# H0FR6.net
KiCad netlist of a schematic drawn in EAGLE
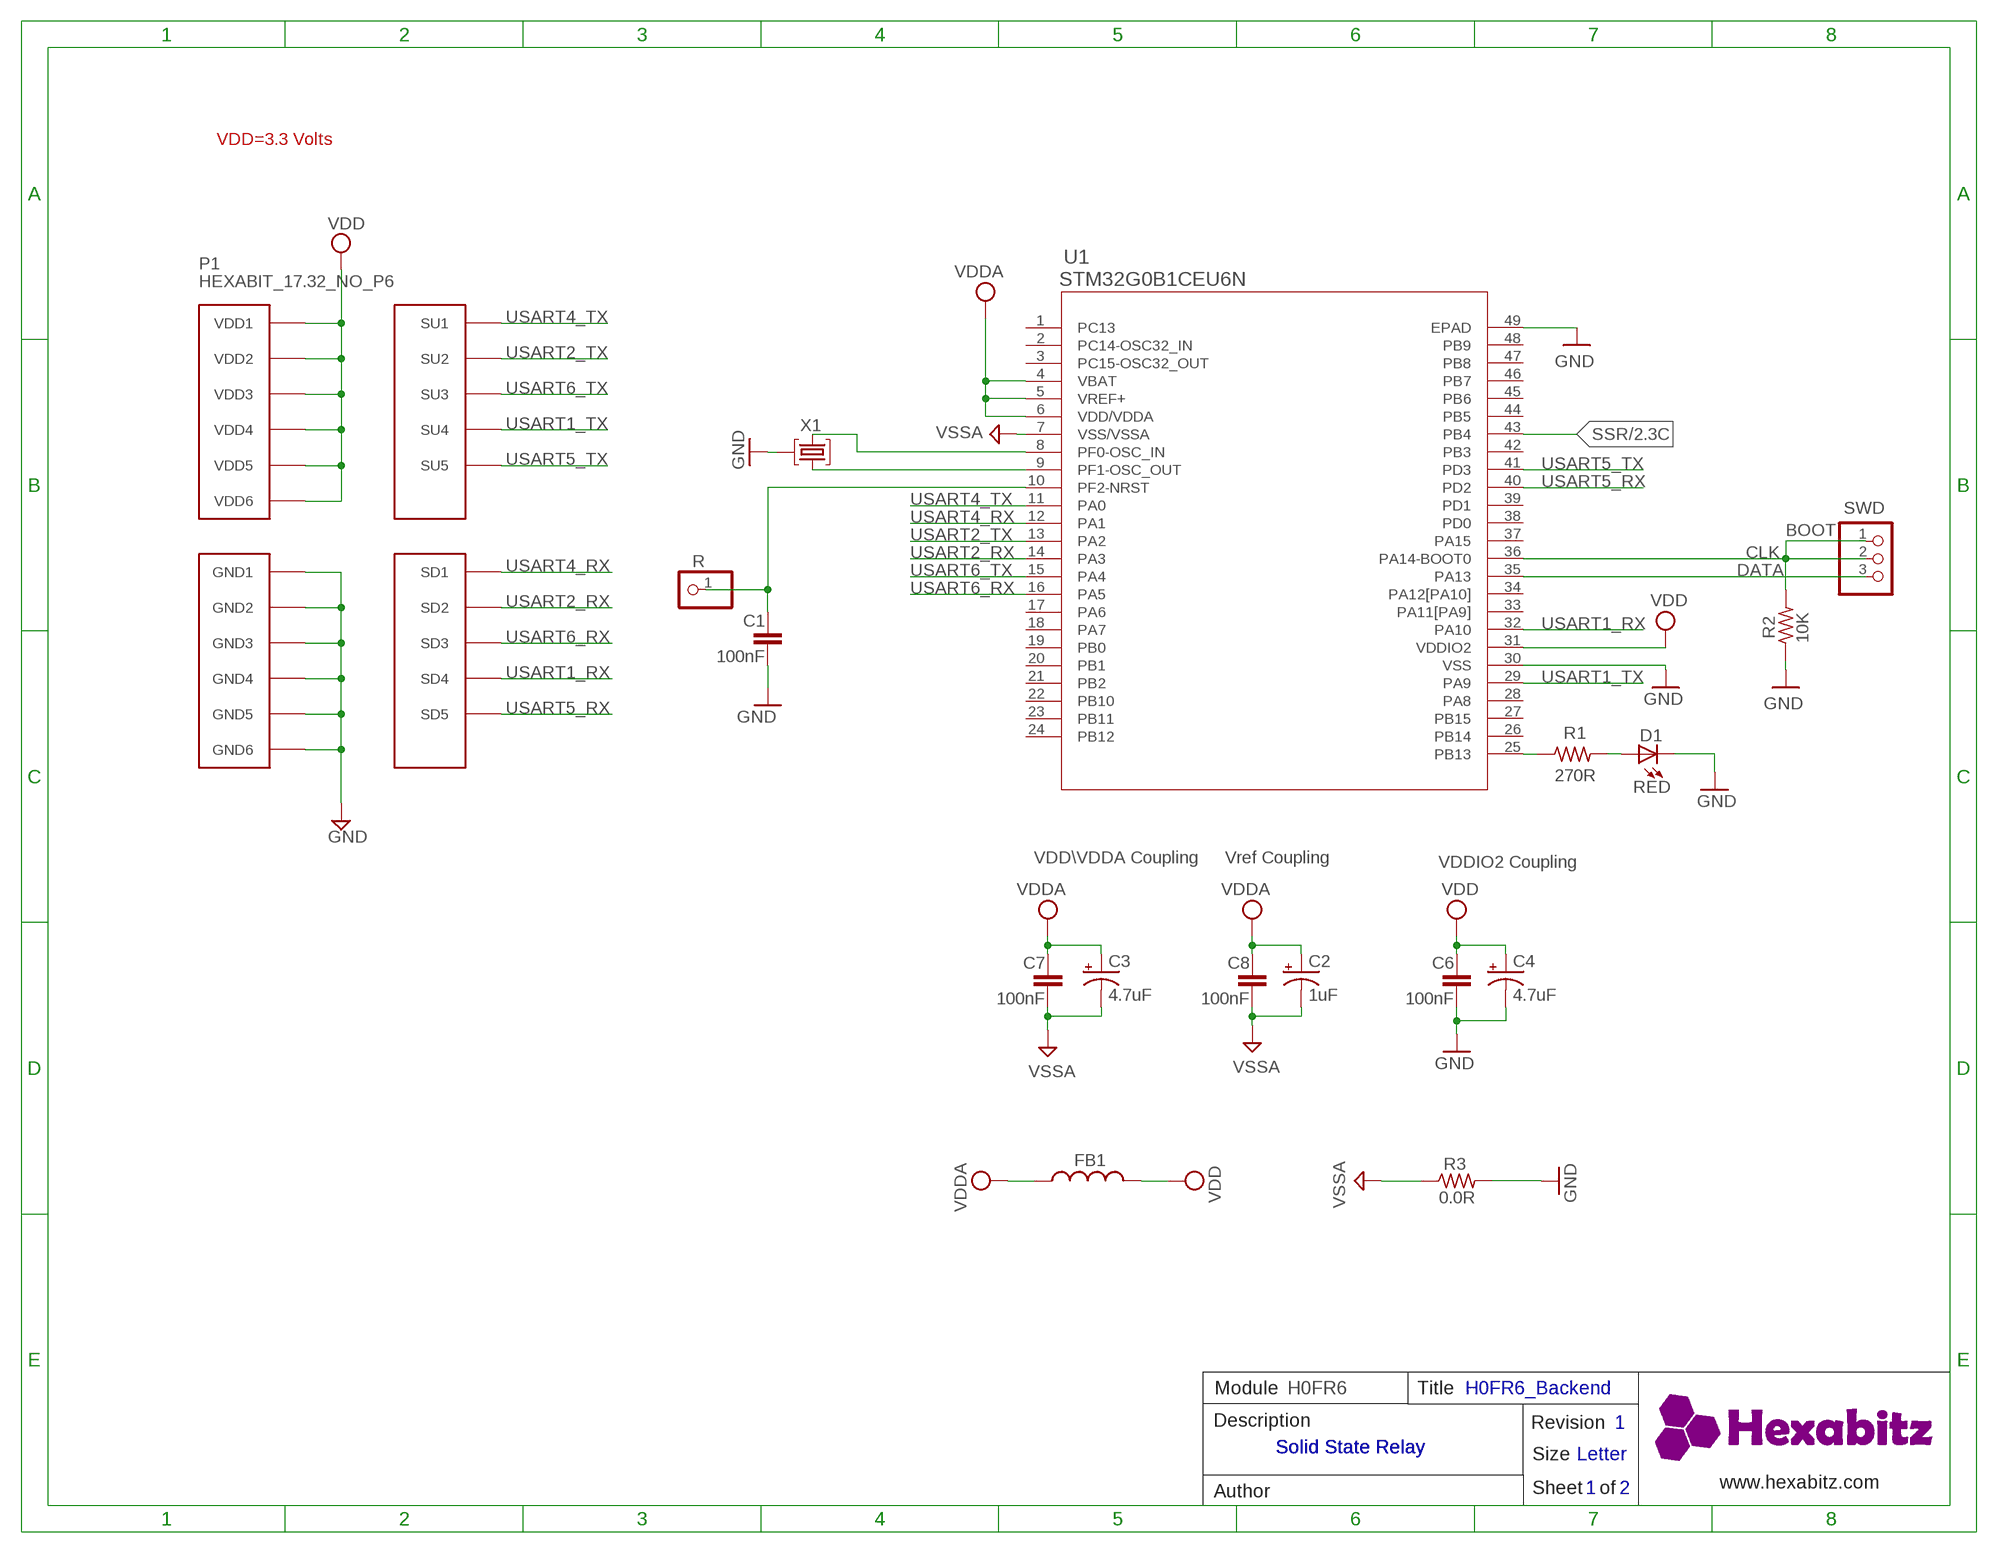
[diagram p0: schematic, sheet 1]
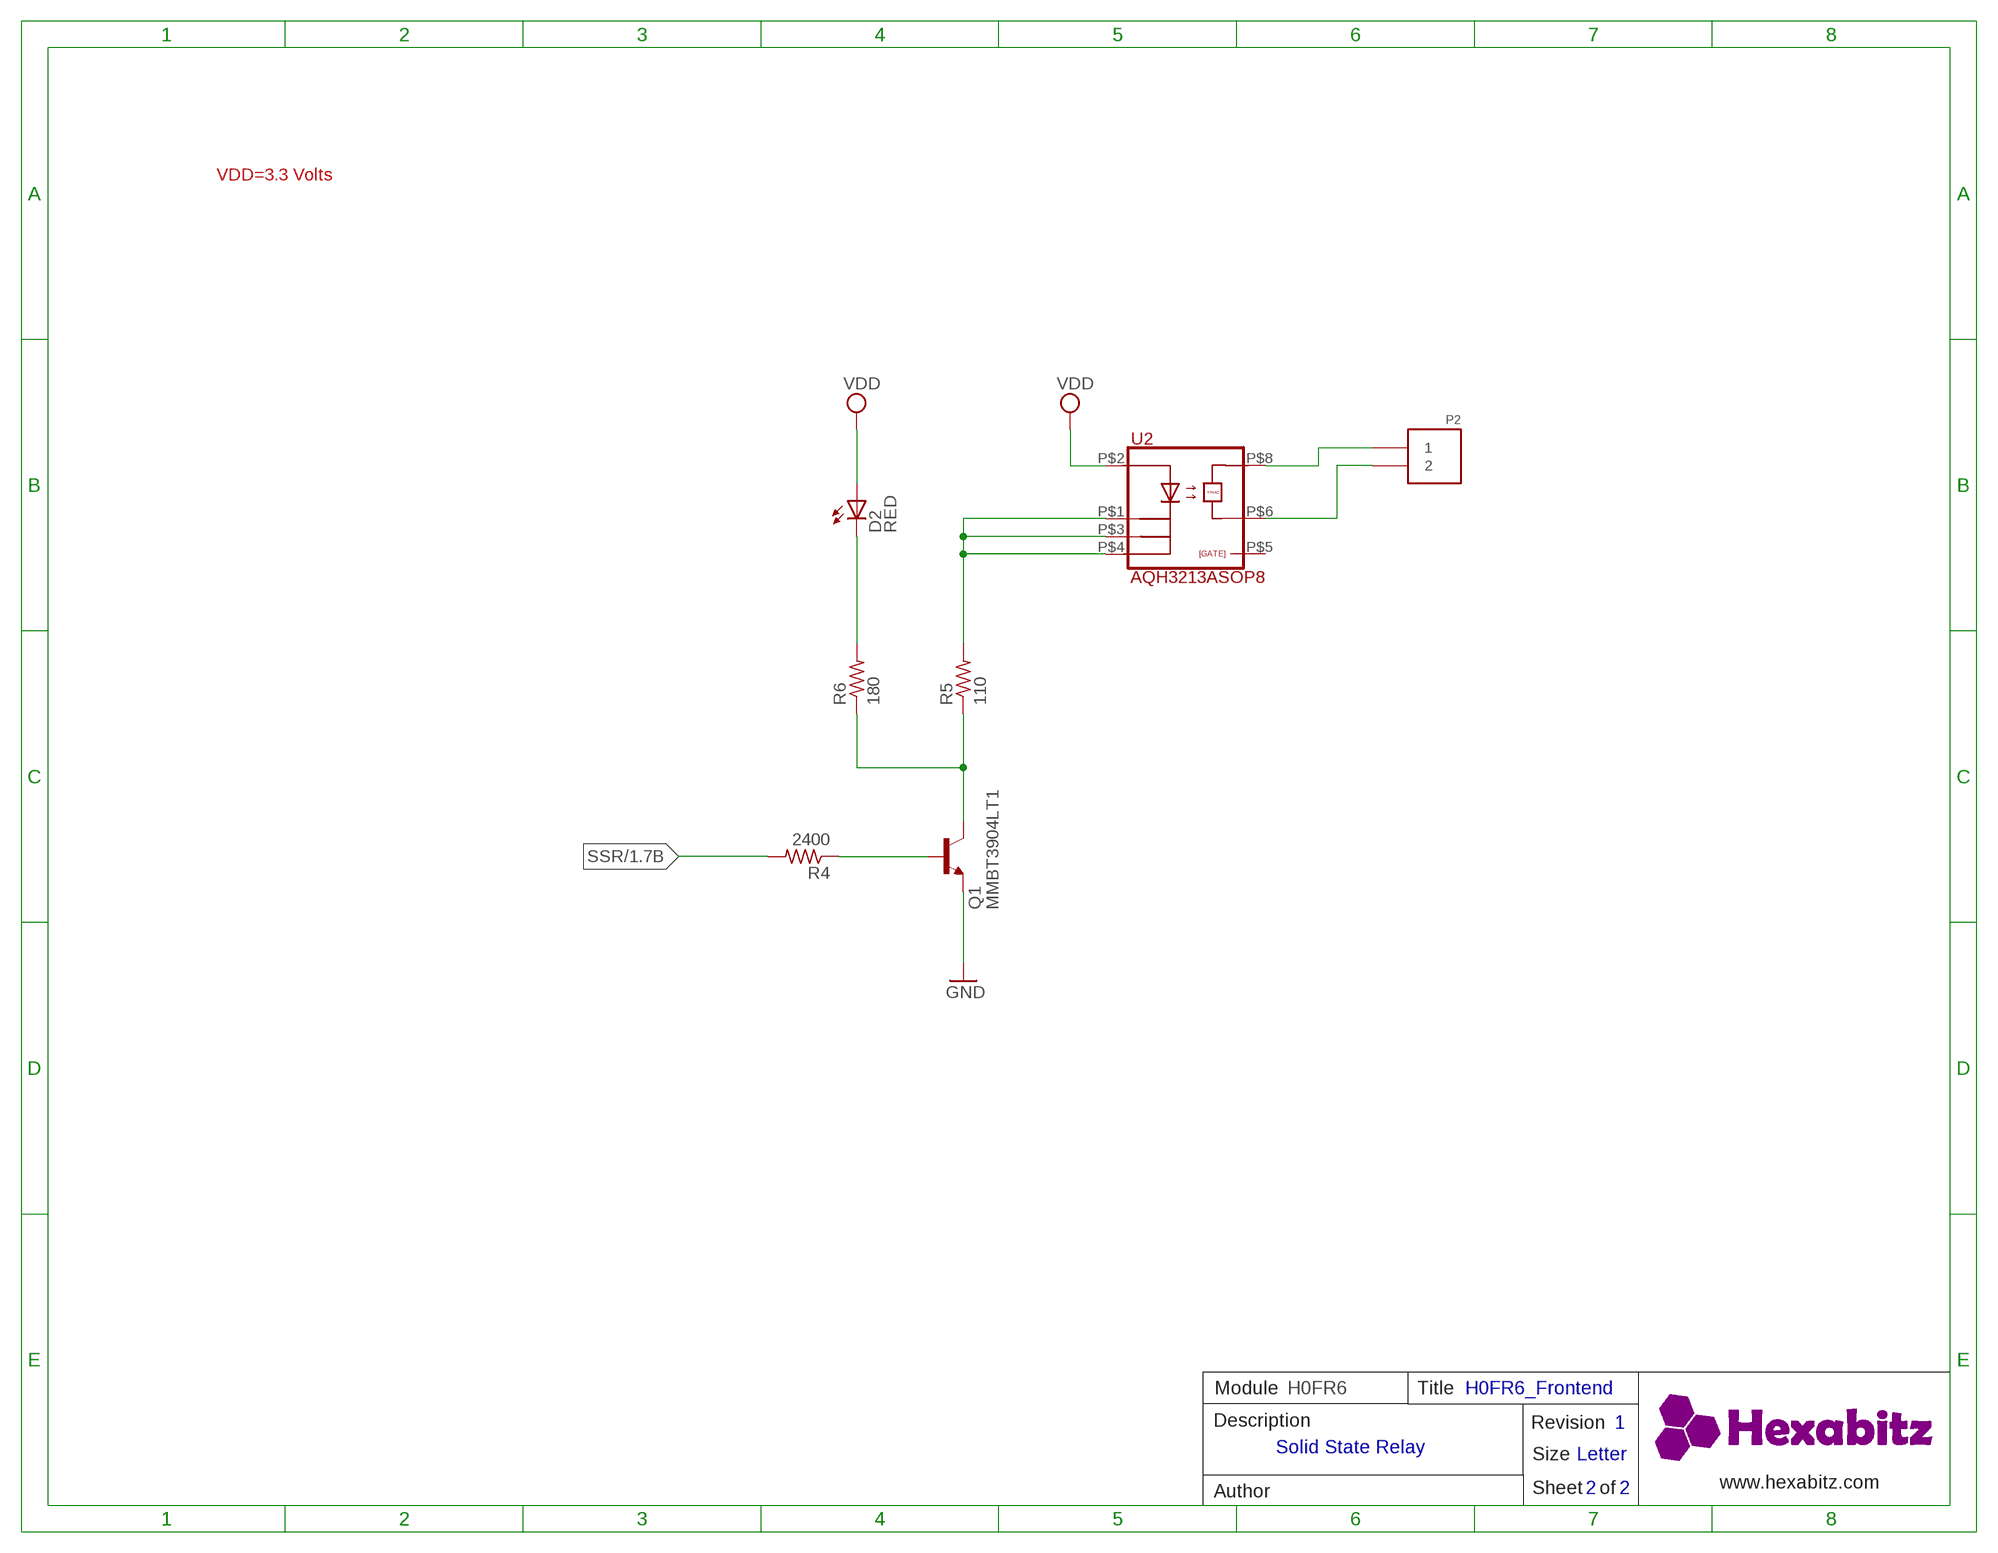
[diagram p1: schematic, sheet 2]

(export (version "E")
  (design (tool "Eeschema 10.0.6"))
  (components
    (comp (ref "D2")
      (value "RED")
      (footprint "eagle-import:VLMS1300-GS08")
      (fields
        (field (name "MPN") "VLMS1300-GS08")
        (field (name "MFN") "Vishay ")
        (field (name "MPN_1") "VLMY1300-GS08")
        (field (name "OCTOPART_URL") "https://octopart.com/vlmy1300-gs08-vishay-21709204")
      )
      (libsource (lib "eagle-import") (part "VLMS1300-GS08"))
    )
    (comp (ref "P2")
      (value "1546111-2")
      (footprint "eagle-import:1546111-2")
      (libsource (lib "eagle-import") (part "1546111-2"))
    )
    (comp (ref "Q1")
      (value "MMBT3904LT1")
      (footprint "eagle-import:MMBT3904LT1")
      (fields
        (field (name "MFN") "ON Semiconductor")
        (field (name "MPN") "MMBT3904LT1G")
        (field (name "OCTOPART_ID") "0bb6c2bc2200d471")
        (field (name "OCTOPART_URL") "http://octopart.com/mmbt3904lt1g-on+semiconductor-3280")
        (field (name "POLARITY") "NPN")
        (field (name "POWER_DISSIPATION") "0.225 W")
        (field (name "VOLTAGE_RATING_DC") "40.0 V")
      )
      (libsource (lib "eagle-import") (part "MMBT3904LT1"))
    )
    (comp (ref "R4")
      (value "2400")
      (footprint "eagle-import:R-0603")
      (fields
        (field (name "MFN") "Yageo")
        (field (name "MPN") "RC0603JR-070RL")
        (field (name "OCTOPART_URL") "https://octopart.com/crcw06032k40jnea-vishay-40298967")
        (field (name "RESISTANCE") "2400.0 Ω")
        (field (name "TOLERANCE") "±5%")
      )
      (libsource (lib "eagle-import") (part "R-0603"))
    )
    (comp (ref "R5")
      (value "110")
      (footprint "eagle-import:R-0603")
      (fields
        (field (name "MFN") "Yageo")
        (field (name "MPN") "RC0402FR-07100RL")
        (field (name "OCTOPART_URL") "https://octopart.com/crcw0603110rfkea-vishay-39455532")
        (field (name "RESISTANCE") "110.0 Ω")
        (field (name "TOLERANCE") "±1%")
      )
      (libsource (lib "eagle-import") (part "R-0603"))
    )
    (comp (ref "R6")
      (value "180")
      (footprint "eagle-import:R-0603")
      (fields
        (field (name "MFN") "Yageo")
        (field (name "MPN") "RC0402FR-07100RL")
        (field (name "OCTOPART_URL") "https://octopart.com/erj-3geyj181v-panasonic-55403673")
        (field (name "RESISTANCE") "180.0 Ω")
        (field (name "TOLERANCE") "±5%")
      )
      (libsource (lib "eagle-import") (part "R-0603"))
    )
    (comp (ref "U2")
      (value "AQH3213ASOP8")
      (footprint "eagle-import:AQH3213A")
      (libsource (lib "eagle-import") (part "AQH3213ASOP8"))
    )
    (comp (ref "C1")
      (value "100nF")
      (footprint "eagle-import:C-0603")
      (libsource (lib "eagle-import") (part "C-0603"))
    )
    (comp (ref "C2")
      (value "1uF")
      (footprint "eagle-import:C-0805-POL")
      (libsource (lib "eagle-import") (part "C-0805-POL"))
    )
    (comp (ref "C3")
      (value "4.7uF")
      (footprint "eagle-import:C-0805-POL")
      (libsource (lib "eagle-import") (part "C-0805-POL"))
    )
    (comp (ref "C4")
      (value "4.7uF")
      (footprint "eagle-import:C-0805-POL")
      (libsource (lib "eagle-import") (part "C-0805-POL"))
    )
    (comp (ref "C6")
      (value "100nF")
      (footprint "eagle-import:C-0603")
      (libsource (lib "eagle-import") (part "C-0603"))
    )
    (comp (ref "C7")
      (value "100nF")
      (footprint "eagle-import:C-0603")
      (libsource (lib "eagle-import") (part "C-0603"))
    )
    (comp (ref "C8")
      (value "100nF")
      (footprint "eagle-import:C-0603")
      (libsource (lib "eagle-import") (part "C-0603"))
    )
    (comp (ref "D1")
      (value "RED")
      (footprint "eagle-import:VLMS1300-GS08")
      (fields
        (field (name "MPN") "VLMS1300-GS08")
        (field (name "MFN") "Vishay")
        (field (name "MPN_1") "VLMS1300-GS08")
        (field (name "OCTOPART_URL") "https://octopart.com/vlms1300-gs08-vishay-21709201?r=sp&s=_gcP4_q8T1SC6PJQPTQ9yA")
      )
      (libsource (lib "eagle-import") (part "VLMS1300-GS08"))
    )
    (comp (ref "FB1")
      (value "FB-0603")
      (footprint "eagle-import:FB-0603")
      (libsource (lib "eagle-import") (part "FB-0603"))
    )
    (comp (ref "P1")
      (value "HEXABIT_17.32_NO_P6")
      (footprint "eagle-import:HEXABIT_17.32_NO_P6")
      (libsource (lib "eagle-import") (part "HEXABIT_?_NO_P617.32"))
    )
    (comp (ref "R")
      (value "R")
      (footprint "eagle-import:1X01")
      (fields (field (name "MPN") "87227-1"))
      (libsource (lib "eagle-import") (part "PINHD-1X1"))
    )
    (comp (ref "R1")
      (value "270R")
      (footprint "eagle-import:R-0603")
      (libsource (lib "eagle-import") (part "R-0603"))
    )
    (comp (ref "R2")
      (value "10K")
      (footprint "eagle-import:R-0603")
      (libsource (lib "eagle-import") (part "R-0603"))
    )
    (comp (ref "R3")
      (value "0.0R")
      (footprint "eagle-import:R-0603")
      (libsource (lib "eagle-import") (part "R-0603"))
    )
    (comp (ref "SWD")
      (value "PINHD-1X3")
      (footprint "eagle-import:1X03")
      (libsource (lib "eagle-import") (part "PINHD-1X3"))
    )
    (comp (ref "U1")
      (value "STM32G0B1CEU6N")
      (footprint "eagle-import:HEXABITZ_ICS_QFN_B1CEU6_STM-L")
      (libsource (lib "eagle-import") (part "STM32G0B1CEU6N"))
    )
    (comp (ref "X1")
      (value "XTALL_CSTCE8M00G52")
      (footprint "eagle-import:XTALL_CSTCE8M00G52")
      (fields (field (name "MPN") "CSTCE8M00G52Z-R0"))
      (libsource (lib "eagle-import") (part "XTALL_CSTCE8M00G52"))
    )
  )
  (nets
    (net (code "1") (name "CLK") (class "Default")
      (node (ref "R2") (pin "2") (pinfunction "2_2") (pintype "passive"))
      (node (ref "SWD") (pin "1") (pinfunction "1_1") (pintype "passive"))
      (node (ref "SWD") (pin "2") (pinfunction "2_2") (pintype "passive"))
      (node (ref "U1") (pin "36") (pinfunction "PA14-BOOT0_36") (pintype "bidirectional"))
    )
    (net (code "2") (name "DATA") (class "Default")
      (node (ref "SWD") (pin "3") (pinfunction "3_3") (pintype "passive"))
      (node (ref "U1") (pin "35") (pinfunction "PA13_35") (pintype "bidirectional"))
    )
    (net (code "3") (name "GND") (class "Default")
      (node (ref "C1") (pin "2") (pinfunction "2_2") (pintype "passive"))
      (node (ref "C4") (pin "2") (pinfunction "-_2") (pintype "passive"))
      (node (ref "C6") (pin "2") (pinfunction "2_2") (pintype "passive"))
      (node (ref "D1") (pin "C") (pinfunction "C_C") (pintype "passive"))
      (node (ref "P1") (pin "PAD_PD10") (pinfunction "GND4_PAD_PD10") (pintype "power_in"))
      (node (ref "P1") (pin "PAD_PD11") (pinfunction "GND5_PAD_PD11") (pintype "power_in"))
      (node (ref "P1") (pin "PAD_PD12") (pinfunction "GND6_PAD_PD12") (pintype "power_in"))
      (node (ref "P1") (pin "PAD_PD7") (pinfunction "GND1_PAD_PD7") (pintype "power_in"))
      (node (ref "P1") (pin "PAD_PD8") (pinfunction "GND2_PAD_PD8") (pintype "power_in"))
      (node (ref "P1") (pin "PAD_PD9") (pinfunction "GND3_PAD_PD9") (pintype "power_in"))
      (node (ref "Q1") (pin "2") (pinfunction "E_2") (pintype "passive"))
      (node (ref "R2") (pin "1") (pinfunction "1_1") (pintype "passive"))
      (node (ref "R3") (pin "2") (pinfunction "2_2") (pintype "passive"))
      (node (ref "U1") (pin "30") (pinfunction "VSS_30") (pintype "passive"))
      (node (ref "U1") (pin "49") (pinfunction "EPAD_49") (pintype "passive"))
      (node (ref "X1") (pin "P$2") (pinfunction "2_P$2") (pintype "passive"))
    )
    (net (code "4") (name "Net-(D1-PadA)") (class "Default")
      (node (ref "D1") (pin "A") (pinfunction "A_A") (pintype "passive"))
      (node (ref "R1") (pin "2") (pinfunction "2_2") (pintype "passive"))
    )
    (net (code "5") (name "Net-(D2-PadC)") (class "Default")
      (node (ref "D2") (pin "C") (pinfunction "C_C") (pintype "passive"))
      (node (ref "R6") (pin "2") (pinfunction "2_2") (pintype "passive"))
    )
    (net (code "6") (name "Net-(P2-Pad2)") (class "Default")
      (node (ref "P2") (pin "2") (pinfunction "2_2") (pintype "power_in"))
      (node (ref "U2") (pin "P$6") (pinfunction "P$6_P$6") (pintype "bidirectional"))
    )
    (net (code "7") (name "Net-(Q1-B)") (class "Default")
      (node (ref "Q1") (pin "1") (pinfunction "B_1") (pintype "passive"))
      (node (ref "R4") (pin "1") (pinfunction "1_1") (pintype "passive"))
    )
    (net (code "8") (name "Net-(Q1-C)") (class "Default")
      (node (ref "Q1") (pin "3") (pinfunction "C_3") (pintype "passive"))
      (node (ref "R5") (pin "1") (pinfunction "1_1") (pintype "passive"))
      (node (ref "R6") (pin "1") (pinfunction "1_1") (pintype "passive"))
    )
    (net (code "9") (name "Net-(R5-Pad2)") (class "Default")
      (node (ref "R5") (pin "2") (pinfunction "2_2") (pintype "passive"))
      (node (ref "U2") (pin "P$1") (pinfunction "P$1_P$1") (pintype "bidirectional"))
      (node (ref "U2") (pin "P$3") (pinfunction "P$3_P$3") (pintype "bidirectional"))
      (node (ref "U2") (pin "P$4") (pinfunction "P$4_P$4") (pintype "bidirectional"))
    )
    (net (code "10") (name "Net-(U1-PB13)") (class "Default")
      (node (ref "R1") (pin "1") (pinfunction "1_1") (pintype "passive"))
      (node (ref "U1") (pin "25") (pinfunction "PB13_25") (pintype "bidirectional"))
    )
    (net (code "11") (name "Net-(U1-PF0-OSC_IN)") (class "Default")
      (node (ref "U1") (pin "8") (pinfunction "PF0-OSC_IN_8") (pintype "bidirectional"))
      (node (ref "X1") (pin "P$3") (pinfunction "3_P$3") (pintype "passive"))
    )
    (net (code "12") (name "Net-(U1-PF1-OSC_OUT)") (class "Default")
      (node (ref "U1") (pin "9") (pinfunction "PF1-OSC_OUT_9") (pintype "bidirectional"))
      (node (ref "X1") (pin "P$1") (pinfunction "1_P$1") (pintype "passive"))
    )
    (net (code "13") (name "Net-(U1-PF2-NRST)") (class "Default")
      (node (ref "C1") (pin "1") (pinfunction "1_1") (pintype "passive"))
      (node (ref "R") (pin "1") (pinfunction "1_1") (pintype "passive"))
      (node (ref "U1") (pin "10") (pinfunction "PF2-NRST_10") (pintype "bidirectional"))
    )
    (net (code "14") (name "Net-(U2-P$7)") (class "Default")
      (node (ref "P2") (pin "1") (pinfunction "1_1") (pintype "power_in"))
      (node (ref "U2") (pin "P$8") (pinfunction "P$7_P$8") (pintype "bidirectional"))
    )
    (net (code "15") (name "SSR") (class "Default")
      (node (ref "R4") (pin "2") (pinfunction "2_2") (pintype "passive"))
      (node (ref "U1") (pin "43") (pinfunction "PB4_43") (pintype "bidirectional"))
    )
    (net (code "16") (name "USART1_RX") (class "Default")
      (node (ref "P1") (pin "PAD_PD4") (pinfunction "SD4_PAD_PD4") (pintype "bidirectional"))
      (node (ref "U1") (pin "32") (pinfunction "PA10_32") (pintype "bidirectional"))
    )
    (net (code "17") (name "USART1_TX") (class "Default")
      (node (ref "P1") (pin "PAD_PU4") (pinfunction "SU4_PAD_PU4") (pintype "bidirectional"))
      (node (ref "U1") (pin "29") (pinfunction "PA9_29") (pintype "bidirectional"))
    )
    (net (code "18") (name "USART2_RX") (class "Default")
      (node (ref "P1") (pin "PAD_PD2") (pinfunction "SD2_PAD_PD2") (pintype "bidirectional"))
      (node (ref "U1") (pin "14") (pinfunction "PA3_14") (pintype "bidirectional"))
    )
    (net (code "19") (name "USART2_TX") (class "Default")
      (node (ref "P1") (pin "PAD_PU2") (pinfunction "SU2_PAD_PU2") (pintype "bidirectional"))
      (node (ref "U1") (pin "13") (pinfunction "PA2_13") (pintype "bidirectional"))
    )
    (net (code "20") (name "USART4_RX") (class "Default")
      (node (ref "P1") (pin "PAD_PD1") (pinfunction "SD1_PAD_PD1") (pintype "bidirectional"))
      (node (ref "U1") (pin "12") (pinfunction "PA1_12") (pintype "bidirectional"))
    )
    (net (code "21") (name "USART4_TX") (class "Default")
      (node (ref "P1") (pin "PAD_PU1") (pinfunction "SU1_PAD_PU1") (pintype "bidirectional"))
      (node (ref "U1") (pin "11") (pinfunction "PA0_11") (pintype "bidirectional"))
    )
    (net (code "22") (name "USART5_RX") (class "Default")
      (node (ref "P1") (pin "PAD_PD5") (pinfunction "SD5_PAD_PD5") (pintype "bidirectional"))
      (node (ref "U1") (pin "40") (pinfunction "PD2_40") (pintype "bidirectional"))
    )
    (net (code "23") (name "USART5_TX") (class "Default")
      (node (ref "P1") (pin "PAD_PU5") (pinfunction "SU5_PAD_PU5") (pintype "bidirectional"))
      (node (ref "U1") (pin "41") (pinfunction "PD3_41") (pintype "bidirectional"))
    )
    (net (code "24") (name "USART6_RX") (class "Default")
      (node (ref "P1") (pin "PAD_PD3") (pinfunction "SD3_PAD_PD3") (pintype "bidirectional"))
      (node (ref "U1") (pin "16") (pinfunction "PA5_16") (pintype "bidirectional"))
    )
    (net (code "25") (name "USART6_TX") (class "Default")
      (node (ref "P1") (pin "PAD_PU3") (pinfunction "SU3_PAD_PU3") (pintype "bidirectional"))
      (node (ref "U1") (pin "15") (pinfunction "PA4_15") (pintype "bidirectional"))
    )
    (net (code "26") (name "VDD") (class "Default")
      (node (ref "C4") (pin "1") (pinfunction "+_1") (pintype "passive"))
      (node (ref "C6") (pin "1") (pinfunction "1_1") (pintype "passive"))
      (node (ref "D2") (pin "A") (pinfunction "A_A") (pintype "passive"))
      (node (ref "FB1") (pin "2") (pinfunction "2_2") (pintype "passive"))
      (node (ref "P1") (pin "PAD_PU10") (pinfunction "VDD4_PAD_PU10") (pintype "power_in"))
      (node (ref "P1") (pin "PAD_PU11") (pinfunction "VDD5_PAD_PU11") (pintype "power_in"))
      (node (ref "P1") (pin "PAD_PU12") (pinfunction "VDD6_PAD_PU12") (pintype "power_in"))
      (node (ref "P1") (pin "PAD_PU7") (pinfunction "VDD1_PAD_PU7") (pintype "power_in"))
      (node (ref "P1") (pin "PAD_PU8") (pinfunction "VDD2_PAD_PU8") (pintype "power_in"))
      (node (ref "P1") (pin "PAD_PU9") (pinfunction "VDD3_PAD_PU9") (pintype "power_in"))
      (node (ref "U1") (pin "31") (pinfunction "VDDIO2_31") (pintype "power_in"))
      (node (ref "U2") (pin "P$2") (pinfunction "P$2_P$2") (pintype "bidirectional"))
    )
    (net (code "27") (name "VDDA") (class "Default")
      (node (ref "C2") (pin "1") (pinfunction "+_1") (pintype "passive"))
      (node (ref "C3") (pin "1") (pinfunction "+_1") (pintype "passive"))
      (node (ref "C7") (pin "1") (pinfunction "1_1") (pintype "passive"))
      (node (ref "C8") (pin "1") (pinfunction "1_1") (pintype "passive"))
      (node (ref "FB1") (pin "1") (pinfunction "1_1") (pintype "passive"))
      (node (ref "U1") (pin "4") (pinfunction "VBAT_4") (pintype "power_in"))
      (node (ref "U1") (pin "5") (pinfunction "VREF+_5") (pintype "power_in"))
      (node (ref "U1") (pin "6") (pinfunction "VDD/VDDA_6") (pintype "power_in"))
    )
    (net (code "28") (name "VSSA") (class "Default")
      (node (ref "C2") (pin "2") (pinfunction "-_2") (pintype "passive"))
      (node (ref "C3") (pin "2") (pinfunction "-_2") (pintype "passive"))
      (node (ref "C7") (pin "2") (pinfunction "2_2") (pintype "passive"))
      (node (ref "C8") (pin "2") (pinfunction "2_2") (pintype "passive"))
      (node (ref "R3") (pin "1") (pinfunction "1_1") (pintype "passive"))
      (node (ref "U1") (pin "7") (pinfunction "VSS/VSSA_7") (pintype "passive"))
    )
    (net (code "29") (name "unconnected-(U1-PA6-Pad17)") (class "Default")
      (node (ref "U1") (pin "17") (pinfunction "PA6_17") (pintype "bidirectional"))
    )
    (net (code "30") (name "unconnected-(U1-PA7-Pad18)") (class "Default")
      (node (ref "U1") (pin "18") (pinfunction "PA7_18") (pintype "bidirectional"))
    )
    (net (code "31") (name "unconnected-(U1-PA8-Pad28)") (class "Default")
      (node (ref "U1") (pin "28") (pinfunction "PA8_28") (pintype "bidirectional"))
    )
    (net (code "32") (name "unconnected-(U1-PA11[PA9]-Pad33)") (class "Default")
      (node (ref "U1") (pin "33") (pinfunction "PA11[PA9]_33") (pintype "bidirectional"))
    )
    (net (code "33") (name "unconnected-(U1-PA12[PA10]-Pad34)") (class "Default")
      (node (ref "U1") (pin "34") (pinfunction "PA12[PA10]_34") (pintype "bidirectional"))
    )
    (net (code "34") (name "unconnected-(U1-PA15-Pad37)") (class "Default")
      (node (ref "U1") (pin "37") (pinfunction "PA15_37") (pintype "bidirectional"))
    )
    (net (code "35") (name "unconnected-(U1-PB0-Pad19)") (class "Default")
      (node (ref "U1") (pin "19") (pinfunction "PB0_19") (pintype "bidirectional"))
    )
    (net (code "36") (name "unconnected-(U1-PB1-Pad20)") (class "Default")
      (node (ref "U1") (pin "20") (pinfunction "PB1_20") (pintype "bidirectional"))
    )
    (net (code "37") (name "unconnected-(U1-PB2-Pad21)") (class "Default")
      (node (ref "U1") (pin "21") (pinfunction "PB2_21") (pintype "bidirectional"))
    )
    (net (code "38") (name "unconnected-(U1-PB3-Pad42)") (class "Default")
      (node (ref "U1") (pin "42") (pinfunction "PB3_42") (pintype "bidirectional"))
    )
    (net (code "39") (name "unconnected-(U1-PB5-Pad44)") (class "Default")
      (node (ref "U1") (pin "44") (pinfunction "PB5_44") (pintype "bidirectional"))
    )
    (net (code "40") (name "unconnected-(U1-PB6-Pad45)") (class "Default")
      (node (ref "U1") (pin "45") (pinfunction "PB6_45") (pintype "bidirectional"))
    )
    (net (code "41") (name "unconnected-(U1-PB7-Pad46)") (class "Default")
      (node (ref "U1") (pin "46") (pinfunction "PB7_46") (pintype "bidirectional"))
    )
    (net (code "42") (name "unconnected-(U1-PB8-Pad47)") (class "Default")
      (node (ref "U1") (pin "47") (pinfunction "PB8_47") (pintype "bidirectional"))
    )
    (net (code "43") (name "unconnected-(U1-PB9-Pad48)") (class "Default")
      (node (ref "U1") (pin "48") (pinfunction "PB9_48") (pintype "bidirectional"))
    )
    (net (code "44") (name "unconnected-(U1-PB10-Pad22)") (class "Default")
      (node (ref "U1") (pin "22") (pinfunction "PB10_22") (pintype "bidirectional"))
    )
    (net (code "45") (name "unconnected-(U1-PB11-Pad23)") (class "Default")
      (node (ref "U1") (pin "23") (pinfunction "PB11_23") (pintype "bidirectional"))
    )
    (net (code "46") (name "unconnected-(U1-PB12-Pad24)") (class "Default")
      (node (ref "U1") (pin "24") (pinfunction "PB12_24") (pintype "bidirectional"))
    )
    (net (code "47") (name "unconnected-(U1-PB14-Pad26)") (class "Default")
      (node (ref "U1") (pin "26") (pinfunction "PB14_26") (pintype "bidirectional"))
    )
    (net (code "48") (name "unconnected-(U1-PB15-Pad27)") (class "Default")
      (node (ref "U1") (pin "27") (pinfunction "PB15_27") (pintype "bidirectional"))
    )
    (net (code "49") (name "unconnected-(U1-PC13-Pad1)") (class "Default")
      (node (ref "U1") (pin "1") (pinfunction "PC13_1") (pintype "bidirectional"))
    )
    (net (code "50") (name "unconnected-(U1-PC14-OSC32_IN-Pad2)") (class "Default")
      (node (ref "U1") (pin "2") (pinfunction "PC14-OSC32_IN_2") (pintype "bidirectional"))
    )
    (net (code "51") (name "unconnected-(U1-PC15-OSC32_OUT-Pad3)") (class "Default")
      (node (ref "U1") (pin "3") (pinfunction "PC15-OSC32_OUT_3") (pintype "bidirectional"))
    )
    (net (code "52") (name "unconnected-(U1-PD0-Pad38)") (class "Default")
      (node (ref "U1") (pin "38") (pinfunction "PD0_38") (pintype "bidirectional"))
    )
    (net (code "53") (name "unconnected-(U1-PD1-Pad39)") (class "Default")
      (node (ref "U1") (pin "39") (pinfunction "PD1_39") (pintype "bidirectional"))
    )
    (net (code "54") (name "unconnected-(U2-PadP$5)") (class "Default")
      (node (ref "U2") (pin "P$5") (pinfunction "P$5_P$5") (pintype "bidirectional"))
    )
  )
)
